# Black_Box.net
KiCad netlist of a schematic drawn in EAGLE
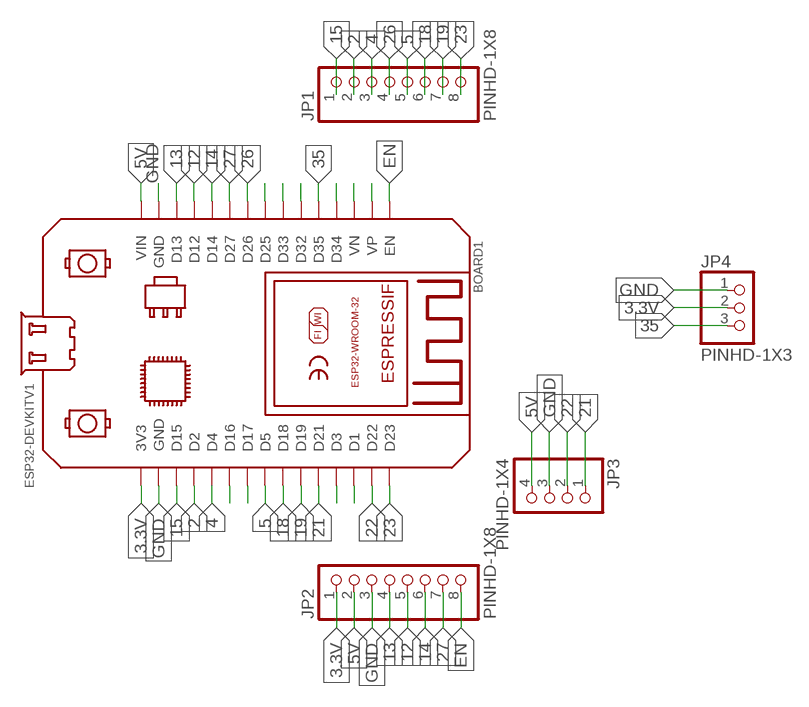
[diagram p0: schematic, sheet 1]

(export (version "E")
  (design (tool "Eeschema 10.0.6"))
  (components
    (comp (ref "BOARD1")
      (value "ESP32DEVKITV1")
      (footprint "eagle-import:ESP32-DEVKITV1")
      (libsource (lib "eagle-import") (part "ESP32DEVKITV1"))
    )
    (comp (ref "JP1")
      (value "PINHD-1X8")
      (footprint "eagle-import:1X08")
      (libsource (lib "eagle-import") (part "PINHD-1X8"))
    )
    (comp (ref "JP2")
      (value "PINHD-1X8")
      (footprint "eagle-import:1X08")
      (libsource (lib "eagle-import") (part "PINHD-1X8"))
    )
    (comp (ref "JP3")
      (value "PINHD-1X4")
      (footprint "eagle-import:1X04")
      (libsource (lib "eagle-import") (part "PINHD-1X4"))
    )
    (comp (ref "JP4")
      (value "PINHD-1X3")
      (footprint "eagle-import:1X03")
      (libsource (lib "eagle-import") (part "PINHD-1X3"))
    )
  )
  (nets
    (net (code "1") (name "2") (class "Default")
      (node (ref "BOARD1") (pin "D2") (pinfunction "D2_D2") (pintype "bidirectional"))
      (node (ref "JP1") (pin "2") (pinfunction "2_2") (pintype "passive"))
    )
    (net (code "2") (name "3.3V") (class "Default")
      (node (ref "BOARD1") (pin "3V3") (pinfunction "3V3_3V3") (pintype "bidirectional"))
      (node (ref "JP2") (pin "1") (pinfunction "1_1") (pintype "passive"))
      (node (ref "JP4") (pin "2") (pinfunction "2_2") (pintype "passive"))
    )
    (net (code "3") (name "4") (class "Default")
      (node (ref "BOARD1") (pin "D4") (pinfunction "D4_D4") (pintype "bidirectional"))
      (node (ref "JP1") (pin "3") (pinfunction "3_3") (pintype "passive"))
    )
    (net (code "4") (name "5") (class "Default")
      (node (ref "BOARD1") (pin "D5") (pinfunction "D5_D5") (pintype "bidirectional"))
      (node (ref "JP1") (pin "5") (pinfunction "5_5") (pintype "passive"))
    )
    (net (code "5") (name "5V") (class "Default")
      (node (ref "BOARD1") (pin "VIN") (pinfunction "VIN_VIN") (pintype "bidirectional"))
      (node (ref "JP2") (pin "2") (pinfunction "2_2") (pintype "passive"))
      (node (ref "JP3") (pin "4") (pinfunction "4_4") (pintype "passive"))
    )
    (net (code "6") (name "12") (class "Default")
      (node (ref "BOARD1") (pin "D12") (pinfunction "D12_D12") (pintype "bidirectional"))
      (node (ref "JP2") (pin "5") (pinfunction "5_5") (pintype "passive"))
    )
    (net (code "7") (name "13") (class "Default")
      (node (ref "BOARD1") (pin "D13") (pinfunction "D13_D13") (pintype "bidirectional"))
      (node (ref "JP2") (pin "4") (pinfunction "4_4") (pintype "passive"))
    )
    (net (code "8") (name "14") (class "Default")
      (node (ref "BOARD1") (pin "D14") (pinfunction "D14_D14") (pintype "bidirectional"))
      (node (ref "JP2") (pin "6") (pinfunction "6_6") (pintype "passive"))
    )
    (net (code "9") (name "15") (class "Default")
      (node (ref "BOARD1") (pin "D15") (pinfunction "D15_D15") (pintype "bidirectional"))
      (node (ref "JP1") (pin "1") (pinfunction "1_1") (pintype "passive"))
    )
    (net (code "10") (name "18") (class "Default")
      (node (ref "BOARD1") (pin "D18") (pinfunction "D18_D18") (pintype "bidirectional"))
      (node (ref "JP1") (pin "6") (pinfunction "6_6") (pintype "passive"))
    )
    (net (code "11") (name "19") (class "Default")
      (node (ref "BOARD1") (pin "D19") (pinfunction "D19_D19") (pintype "bidirectional"))
      (node (ref "JP1") (pin "7") (pinfunction "7_7") (pintype "passive"))
    )
    (net (code "12") (name "21") (class "Default")
      (node (ref "BOARD1") (pin "D21") (pinfunction "D21_D21") (pintype "bidirectional"))
      (node (ref "JP3") (pin "1") (pinfunction "1_1") (pintype "passive"))
    )
    (net (code "13") (name "22") (class "Default")
      (node (ref "BOARD1") (pin "D22") (pinfunction "D22_D22") (pintype "bidirectional"))
      (node (ref "JP3") (pin "2") (pinfunction "2_2") (pintype "passive"))
    )
    (net (code "14") (name "23") (class "Default")
      (node (ref "BOARD1") (pin "D23") (pinfunction "D23_D23") (pintype "bidirectional"))
      (node (ref "JP1") (pin "8") (pinfunction "8_8") (pintype "passive"))
    )
    (net (code "15") (name "26") (class "Default")
      (node (ref "BOARD1") (pin "D26") (pinfunction "D26_D26") (pintype "bidirectional"))
      (node (ref "JP1") (pin "4") (pinfunction "4_4") (pintype "passive"))
    )
    (net (code "16") (name "27") (class "Default")
      (node (ref "BOARD1") (pin "D27") (pinfunction "D27_D27") (pintype "bidirectional"))
      (node (ref "JP2") (pin "7") (pinfunction "7_7") (pintype "passive"))
    )
    (net (code "17") (name "35") (class "Default")
      (node (ref "BOARD1") (pin "D35") (pinfunction "D35_D35") (pintype "bidirectional"))
      (node (ref "JP4") (pin "3") (pinfunction "3_3") (pintype "passive"))
    )
    (net (code "18") (name "EN") (class "Default")
      (node (ref "BOARD1") (pin "EN") (pinfunction "EN_EN") (pintype "bidirectional"))
      (node (ref "JP2") (pin "8") (pinfunction "8_8") (pintype "passive"))
    )
    (net (code "19") (name "GND") (class "Default")
      (node (ref "BOARD1") (pin "GND") (pinfunction "GND_GND") (pintype "bidirectional"))
      (node (ref "BOARD1") (pin "GND@1") (pinfunction "GND_GND@1") (pintype "bidirectional"))
      (node (ref "JP2") (pin "3") (pinfunction "3_3") (pintype "passive"))
      (node (ref "JP3") (pin "3") (pinfunction "3_3") (pintype "passive"))
      (node (ref "JP4") (pin "1") (pinfunction "1_1") (pintype "passive"))
    )
    (net (code "20") (name "unconnected-(BOARD1-PadD1)") (class "Default")
      (node (ref "BOARD1") (pin "D1") (pinfunction "D1_D1") (pintype "bidirectional"))
    )
    (net (code "21") (name "unconnected-(BOARD1-PadD3)") (class "Default")
      (node (ref "BOARD1") (pin "D3") (pinfunction "D3_D3") (pintype "bidirectional"))
    )
    (net (code "22") (name "unconnected-(BOARD1-PadD16)") (class "Default")
      (node (ref "BOARD1") (pin "D16") (pinfunction "D16_D16") (pintype "bidirectional"))
    )
    (net (code "23") (name "unconnected-(BOARD1-PadD17)") (class "Default")
      (node (ref "BOARD1") (pin "D17") (pinfunction "D17_D17") (pintype "bidirectional"))
    )
    (net (code "24") (name "unconnected-(BOARD1-PadD25)") (class "Default")
      (node (ref "BOARD1") (pin "D25") (pinfunction "D25_D25") (pintype "bidirectional"))
    )
    (net (code "25") (name "unconnected-(BOARD1-PadD32)") (class "Default")
      (node (ref "BOARD1") (pin "D32") (pinfunction "D32_D32") (pintype "bidirectional"))
    )
    (net (code "26") (name "unconnected-(BOARD1-PadD33)") (class "Default")
      (node (ref "BOARD1") (pin "D33") (pinfunction "D33_D33") (pintype "bidirectional"))
    )
    (net (code "27") (name "unconnected-(BOARD1-PadD34)") (class "Default")
      (node (ref "BOARD1") (pin "D34") (pinfunction "D34_D34") (pintype "bidirectional"))
    )
    (net (code "28") (name "unconnected-(BOARD1-PadVN)") (class "Default")
      (node (ref "BOARD1") (pin "VN") (pinfunction "VN_VN") (pintype "bidirectional"))
    )
    (net (code "29") (name "unconnected-(BOARD1-PadVP)") (class "Default")
      (node (ref "BOARD1") (pin "VP") (pinfunction "VP_VP") (pintype "bidirectional"))
    )
  )
)
